# Cells.net
KiCad netlist of a schematic drawn in Altium Designer
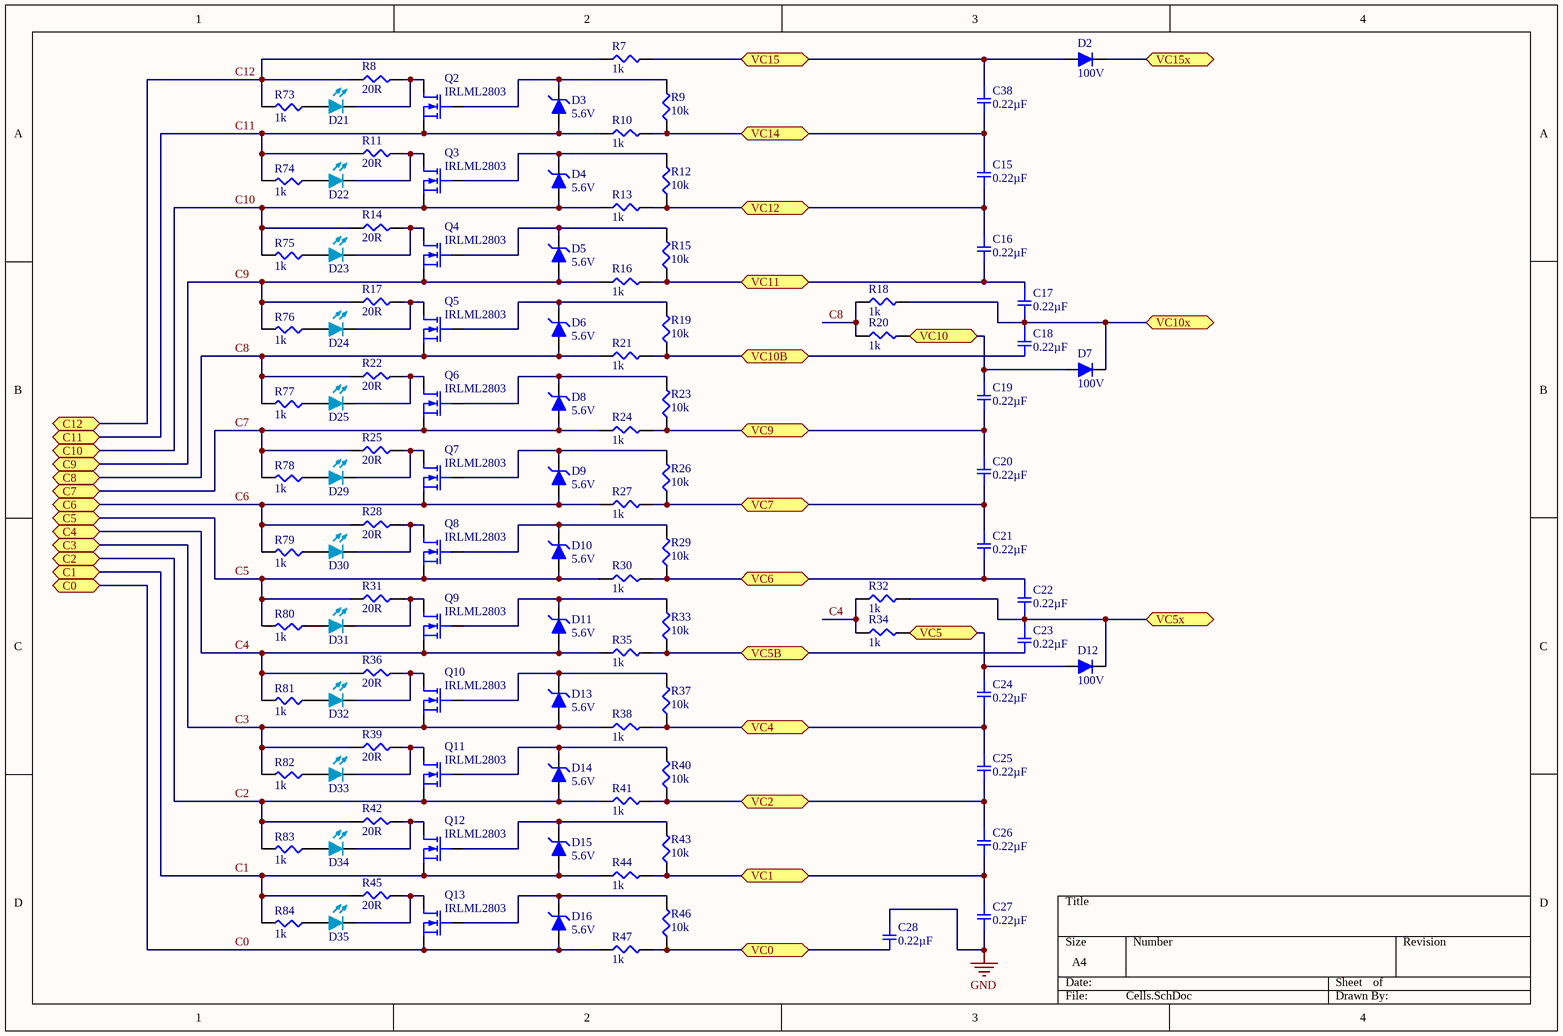
[diagram p0: Cells.SchDoc]

(export (version "E")
  (design (tool "Eeschema 10.0.6"))
  (components
    (comp (ref "C15")
      (value "0.22µF")
      (footprint "SMD-0603C")
      (description "CAP CER 0.22UF 25V X7R 0603")
      (fields
        (field (name "DIGI-KEY PART NUMBER") "490-5797-1-ND")
        (field (name "PART NUMBER") "GCJ188R71E224KA12D")
      )
      (libsource (lib "capacitor_murata_0603") (part "GCJ188R71E224KA12D"))
    )
    (comp (ref "C16")
      (value "0.22µF")
      (footprint "SMD-0603C")
      (description "CAP CER 0.22UF 25V X7R 0603")
      (fields
        (field (name "DIGI-KEY PART NUMBER") "490-5797-1-ND")
        (field (name "PART NUMBER") "GCJ188R71E224KA12D")
      )
      (libsource (lib "capacitor_murata_0603") (part "GCJ188R71E224KA12D"))
    )
    (comp (ref "C17")
      (value "0.22µF")
      (footprint "SMD-0603C")
      (description "CAP CER 0.22UF 25V X7R 0603")
      (fields
        (field (name "DIGI-KEY PART NUMBER") "490-5797-1-ND")
        (field (name "PART NUMBER") "GCJ188R71E224KA12D")
      )
      (libsource (lib "capacitor_murata_0603") (part "GCJ188R71E224KA12D"))
    )
    (comp (ref "C18")
      (value "0.22µF")
      (footprint "SMD-0603C")
      (description "CAP CER 0.22UF 25V X7R 0603")
      (fields
        (field (name "DIGI-KEY PART NUMBER") "490-5797-1-ND")
        (field (name "PART NUMBER") "GCJ188R71E224KA12D")
      )
      (libsource (lib "capacitor_murata_0603") (part "GCJ188R71E224KA12D"))
    )
    (comp (ref "C19")
      (value "0.22µF")
      (footprint "SMD-0603C")
      (description "CAP CER 0.22UF 25V X7R 0603")
      (fields
        (field (name "DIGI-KEY PART NUMBER") "490-5797-1-ND")
        (field (name "PART NUMBER") "GCJ188R71E224KA12D")
      )
      (libsource (lib "capacitor_murata_0603") (part "GCJ188R71E224KA12D"))
    )
    (comp (ref "C20")
      (value "0.22µF")
      (footprint "SMD-0603C")
      (description "CAP CER 0.22UF 25V X7R 0603")
      (fields
        (field (name "DIGI-KEY PART NUMBER") "490-5797-1-ND")
        (field (name "PART NUMBER") "GCJ188R71E224KA12D")
      )
      (libsource (lib "capacitor_murata_0603") (part "GCJ188R71E224KA12D"))
    )
    (comp (ref "C21")
      (value "0.22µF")
      (footprint "SMD-0603C")
      (description "CAP CER 0.22UF 25V X7R 0603")
      (fields
        (field (name "DIGI-KEY PART NUMBER") "490-5797-1-ND")
        (field (name "PART NUMBER") "GCJ188R71E224KA12D")
      )
      (libsource (lib "capacitor_murata_0603") (part "GCJ188R71E224KA12D"))
    )
    (comp (ref "C22")
      (value "0.22µF")
      (footprint "SMD-0603C")
      (description "CAP CER 0.22UF 25V X7R 0603")
      (fields
        (field (name "DIGI-KEY PART NUMBER") "490-5797-1-ND")
        (field (name "PART NUMBER") "GCJ188R71E224KA12D")
      )
      (libsource (lib "capacitor_murata_0603") (part "GCJ188R71E224KA12D"))
    )
    (comp (ref "C23")
      (value "0.22µF")
      (footprint "SMD-0603C")
      (description "CAP CER 0.22UF 25V X7R 0603")
      (fields
        (field (name "DIGI-KEY PART NUMBER") "490-5797-1-ND")
        (field (name "PART NUMBER") "GCJ188R71E224KA12D")
      )
      (libsource (lib "capacitor_murata_0603") (part "GCJ188R71E224KA12D"))
    )
    (comp (ref "C24")
      (value "0.22µF")
      (footprint "SMD-0603C")
      (description "CAP CER 0.22UF 25V X7R 0603")
      (fields
        (field (name "DIGI-KEY PART NUMBER") "490-5797-1-ND")
        (field (name "PART NUMBER") "GCJ188R71E224KA12D")
      )
      (libsource (lib "capacitor_murata_0603") (part "GCJ188R71E224KA12D"))
    )
    (comp (ref "C25")
      (value "0.22µF")
      (footprint "SMD-0603C")
      (description "CAP CER 0.22UF 25V X7R 0603")
      (fields
        (field (name "DIGI-KEY PART NUMBER") "490-5797-1-ND")
        (field (name "PART NUMBER") "GCJ188R71E224KA12D")
      )
      (libsource (lib "capacitor_murata_0603") (part "GCJ188R71E224KA12D"))
    )
    (comp (ref "C26")
      (value "0.22µF")
      (footprint "SMD-0603C")
      (description "CAP CER 0.22UF 25V X7R 0603")
      (fields
        (field (name "DIGI-KEY PART NUMBER") "490-5797-1-ND")
        (field (name "PART NUMBER") "GCJ188R71E224KA12D")
      )
      (libsource (lib "capacitor_murata_0603") (part "GCJ188R71E224KA12D"))
    )
    (comp (ref "C27")
      (value "0.22µF")
      (footprint "SMD-0603C")
      (description "CAP CER 0.22UF 25V X7R 0603")
      (fields
        (field (name "DIGI-KEY PART NUMBER") "490-5797-1-ND")
        (field (name "PART NUMBER") "GCJ188R71E224KA12D")
      )
      (libsource (lib "capacitor_murata_0603") (part "GCJ188R71E224KA12D"))
    )
    (comp (ref "C28")
      (value "0.22µF")
      (footprint "SMD-0603C")
      (description "CAP CER 0.22UF 25V X7R 0603")
      (fields
        (field (name "DIGI-KEY PART NUMBER") "490-5797-1-ND")
        (field (name "PART NUMBER") "GCJ188R71E224KA12D")
      )
      (libsource (lib "capacitor_murata_0603") (part "GCJ188R71E224KA12D"))
    )
    (comp (ref "C38")
      (value "0.22µF")
      (footprint "SMD-0603C")
      (description "CAP CER 0.22UF 25V X7R 0603")
      (fields
        (field (name "DIGI-KEY PART NUMBER") "490-5797-1-ND")
        (field (name "PART NUMBER") "GCJ188R71E224KA12D")
      )
      (libsource (lib "capacitor_murata_0603") (part "GCJ188R71E224KA12D"))
    )
    (comp (ref "D2")
      (value "100V")
      (footprint "SOD-323")
      (description "Diode")
      (libsource (lib "Components") (part "DIODE"))
    )
    (comp (ref "D3")
      (value "5.6V")
      (footprint "SOD-323")
      (description "Zener Diode 5.6V")
      (libsource (lib "Components") (part "ZENER_5V6"))
    )
    (comp (ref "D4")
      (value "5.6V")
      (footprint "SOD-323")
      (description "Zener Diode 5.6V")
      (libsource (lib "Components") (part "ZENER_5V6"))
    )
    (comp (ref "D5")
      (value "5.6V")
      (footprint "SOD-323")
      (description "Zener Diode 5.6V")
      (libsource (lib "Components") (part "ZENER_5V6"))
    )
    (comp (ref "D6")
      (value "5.6V")
      (footprint "SOD-323")
      (description "Zener Diode 5.6V")
      (libsource (lib "Components") (part "ZENER_5V6"))
    )
    (comp (ref "D7")
      (value "100V")
      (footprint "SOD-323")
      (description "Diode")
      (libsource (lib "Components") (part "DIODE"))
    )
    (comp (ref "D8")
      (value "5.6V")
      (footprint "SOD-323")
      (description "Zener Diode 5.6V")
      (libsource (lib "Components") (part "ZENER_5V6"))
    )
    (comp (ref "D9")
      (value "5.6V")
      (footprint "SOD-323")
      (description "Zener Diode 5.6V")
      (libsource (lib "Components") (part "ZENER_5V6"))
    )
    (comp (ref "D10")
      (value "5.6V")
      (footprint "SOD-323")
      (description "Zener Diode 5.6V")
      (libsource (lib "Components") (part "ZENER_5V6"))
    )
    (comp (ref "D11")
      (value "5.6V")
      (footprint "SOD-323")
      (description "Zener Diode 5.6V")
      (libsource (lib "Components") (part "ZENER_5V6"))
    )
    (comp (ref "D12")
      (value "100V")
      (footprint "SOD-323")
      (description "Diode")
      (libsource (lib "Components") (part "DIODE"))
    )
    (comp (ref "D13")
      (value "5.6V")
      (footprint "SOD-323")
      (description "Zener Diode 5.6V")
      (libsource (lib "Components") (part "ZENER_5V6"))
    )
    (comp (ref "D14")
      (value "5.6V")
      (footprint "SOD-323")
      (description "Zener Diode 5.6V")
      (libsource (lib "Components") (part "ZENER_5V6"))
    )
    (comp (ref "D15")
      (value "5.6V")
      (footprint "SOD-323")
      (description "Zener Diode 5.6V")
      (libsource (lib "Components") (part "ZENER_5V6"))
    )
    (comp (ref "D16")
      (value "5.6V")
      (footprint "SOD-323")
      (description "Zener Diode 5.6V")
      (libsource (lib "Components") (part "ZENER_5V6"))
    )
    (comp (ref "D21")
      (value "LED")
      (footprint "LED0603")
      (fields (field (name "PARTNUMBER") "LTST-C193TGKT-5A") (field (name "MANUFACTURER") "Lite-On Inc."))
      (libsource (lib "Components") (part "LED_BLUE"))
    )
    (comp (ref "D22")
      (value "LED")
      (footprint "LED0603")
      (fields (field (name "PARTNUMBER") "LTST-C193TGKT-5A") (field (name "MANUFACTURER") "Lite-On Inc."))
      (libsource (lib "Components") (part "LED_BLUE"))
    )
    (comp (ref "D23")
      (value "LED")
      (footprint "LED0603")
      (fields (field (name "PARTNUMBER") "LTST-C193TGKT-5A") (field (name "MANUFACTURER") "Lite-On Inc."))
      (libsource (lib "Components") (part "LED_BLUE"))
    )
    (comp (ref "D24")
      (value "LED")
      (footprint "LED0603")
      (fields (field (name "PARTNUMBER") "LTST-C193TGKT-5A") (field (name "MANUFACTURER") "Lite-On Inc."))
      (libsource (lib "Components") (part "LED_BLUE"))
    )
    (comp (ref "D25")
      (value "LED")
      (footprint "LED0603")
      (fields (field (name "PARTNUMBER") "LTST-C193TGKT-5A") (field (name "MANUFACTURER") "Lite-On Inc."))
      (libsource (lib "Components") (part "LED_BLUE"))
    )
    (comp (ref "D29")
      (value "LED")
      (footprint "LED0603")
      (fields (field (name "PARTNUMBER") "LTST-C193TGKT-5A") (field (name "MANUFACTURER") "Lite-On Inc."))
      (libsource (lib "Components") (part "LED_BLUE"))
    )
    (comp (ref "D30")
      (value "LED")
      (footprint "LED0603")
      (fields (field (name "PARTNUMBER") "LTST-C193TGKT-5A") (field (name "MANUFACTURER") "Lite-On Inc."))
      (libsource (lib "Components") (part "LED_BLUE"))
    )
    (comp (ref "D31")
      (value "LED")
      (footprint "LED0603")
      (fields (field (name "PARTNUMBER") "LTST-C193TGKT-5A") (field (name "MANUFACTURER") "Lite-On Inc."))
      (libsource (lib "Components") (part "LED_BLUE"))
    )
    (comp (ref "D32")
      (value "LED")
      (footprint "LED0603")
      (fields (field (name "PARTNUMBER") "LTST-C193TGKT-5A") (field (name "MANUFACTURER") "Lite-On Inc."))
      (libsource (lib "Components") (part "LED_BLUE"))
    )
    (comp (ref "D33")
      (value "LED")
      (footprint "LED0603")
      (fields (field (name "PARTNUMBER") "LTST-C193TGKT-5A") (field (name "MANUFACTURER") "Lite-On Inc."))
      (libsource (lib "Components") (part "LED_BLUE"))
    )
    (comp (ref "D34")
      (value "LED")
      (footprint "LED0603")
      (fields (field (name "PARTNUMBER") "LTST-C193TGKT-5A") (field (name "MANUFACTURER") "Lite-On Inc."))
      (libsource (lib "Components") (part "LED_BLUE"))
    )
    (comp (ref "D35")
      (value "LED")
      (footprint "LED0603")
      (fields (field (name "PARTNUMBER") "LTST-C193TGKT-5A") (field (name "MANUFACTURER") "Lite-On Inc."))
      (libsource (lib "Components") (part "LED_BLUE"))
    )
    (comp (ref "Q2")
      (value "IRLML2803")
      (footprint "SOT23-3")
      (description "N-Channel MOSFET")
      (fields (field (name "PUBLISHER") "Altium Limited"))
      (libsource (lib "Components") (part "MOSFET-N"))
    )
    (comp (ref "Q3")
      (value "IRLML2803")
      (footprint "SOT23-3")
      (description "N-Channel MOSFET")
      (fields (field (name "PUBLISHER") "Altium Limited"))
      (libsource (lib "Components") (part "MOSFET-N"))
    )
    (comp (ref "Q4")
      (value "IRLML2803")
      (footprint "SOT23-3")
      (description "N-Channel MOSFET")
      (fields (field (name "PUBLISHER") "Altium Limited"))
      (libsource (lib "Components") (part "MOSFET-N"))
    )
    (comp (ref "Q5")
      (value "IRLML2803")
      (footprint "SOT23-3")
      (description "N-Channel MOSFET")
      (fields (field (name "PUBLISHER") "Altium Limited"))
      (libsource (lib "Components") (part "MOSFET-N"))
    )
    (comp (ref "Q6")
      (value "IRLML2803")
      (footprint "SOT23-3")
      (description "N-Channel MOSFET")
      (fields (field (name "PUBLISHER") "Altium Limited"))
      (libsource (lib "Components") (part "MOSFET-N"))
    )
    (comp (ref "Q7")
      (value "IRLML2803")
      (footprint "SOT23-3")
      (description "N-Channel MOSFET")
      (fields (field (name "PUBLISHER") "Altium Limited"))
      (libsource (lib "Components") (part "MOSFET-N"))
    )
    (comp (ref "Q8")
      (value "IRLML2803")
      (footprint "SOT23-3")
      (description "N-Channel MOSFET")
      (fields (field (name "PUBLISHER") "Altium Limited"))
      (libsource (lib "Components") (part "MOSFET-N"))
    )
    (comp (ref "Q9")
      (value "IRLML2803")
      (footprint "SOT23-3")
      (description "N-Channel MOSFET")
      (fields (field (name "PUBLISHER") "Altium Limited"))
      (libsource (lib "Components") (part "MOSFET-N"))
    )
    (comp (ref "Q10")
      (value "IRLML2803")
      (footprint "SOT23-3")
      (description "N-Channel MOSFET")
      (fields (field (name "PUBLISHER") "Altium Limited"))
      (libsource (lib "Components") (part "MOSFET-N"))
    )
    (comp (ref "Q11")
      (value "IRLML2803")
      (footprint "SOT23-3")
      (description "N-Channel MOSFET")
      (fields (field (name "PUBLISHER") "Altium Limited"))
      (libsource (lib "Components") (part "MOSFET-N"))
    )
    (comp (ref "Q12")
      (value "IRLML2803")
      (footprint "SOT23-3")
      (description "N-Channel MOSFET")
      (fields (field (name "PUBLISHER") "Altium Limited"))
      (libsource (lib "Components") (part "MOSFET-N"))
    )
    (comp (ref "Q13")
      (value "IRLML2803")
      (footprint "SOT23-3")
      (description "N-Channel MOSFET")
      (fields (field (name "PUBLISHER") "Altium Limited"))
      (libsource (lib "Components") (part "MOSFET-N"))
    )
    (comp (ref "R7")
      (value "1k")
      (footprint "SMD-0603-RES")
      (description "RES SMD 1K OHM 1% 1/10W 0603")
      (fields
        (field (name "PART NUMBER") "ERJ-3EKF1001V")
        (field (name "DIGI-KEY PART NUMBER") "P1.00KHCT-ND")
      )
      (libsource (lib "Panasonic_ERJ_0603") (part "ERJ-3EKF1001V"))
    )
    (comp (ref "R8")
      (value "20R")
      (footprint "SMD-1206-RES")
      (description "RES SMD 20 OHM 1% 1/4W 1206")
      (fields
        (field (name "PART NUMBER") "ERJ-8ENF20R0V")
        (field (name "DIGI-KEY PART NUMBER") "P20.0FCT-ND")
      )
      (libsource (lib "Panasonic_ERJ_1206") (part "ERJ-8ENF20R0V"))
    )
    (comp (ref "R9")
      (value "10k")
      (footprint "SMD-0603-RES")
      (description "RES SMD 10K OHM 1% 1/10W 0603")
      (fields
        (field (name "PART NUMBER") "ERJ-3EKF1002V")
        (field (name "DIGI-KEY PART NUMBER") "P10.0KHCT-ND")
      )
      (libsource (lib "Panasonic_ERJ_0603") (part "ERJ-3EKF1002V"))
    )
    (comp (ref "R10")
      (value "1k")
      (footprint "SMD-0603-RES")
      (description "RES SMD 1K OHM 1% 1/10W 0603")
      (fields
        (field (name "PART NUMBER") "ERJ-3EKF1001V")
        (field (name "DIGI-KEY PART NUMBER") "P1.00KHCT-ND")
      )
      (libsource (lib "Panasonic_ERJ_0603") (part "ERJ-3EKF1001V"))
    )
    (comp (ref "R11")
      (value "20R")
      (footprint "SMD-1206-RES")
      (description "RES SMD 20 OHM 1% 1/4W 1206")
      (fields
        (field (name "PART NUMBER") "ERJ-8ENF20R0V")
        (field (name "DIGI-KEY PART NUMBER") "P20.0FCT-ND")
      )
      (libsource (lib "Panasonic_ERJ_1206") (part "ERJ-8ENF20R0V"))
    )
    (comp (ref "R12")
      (value "10k")
      (footprint "SMD-0603-RES")
      (description "RES SMD 10K OHM 1% 1/10W 0603")
      (fields
        (field (name "PART NUMBER") "ERJ-3EKF1002V")
        (field (name "DIGI-KEY PART NUMBER") "P10.0KHCT-ND")
      )
      (libsource (lib "Panasonic_ERJ_0603") (part "ERJ-3EKF1002V"))
    )
    (comp (ref "R13")
      (value "1k")
      (footprint "SMD-0603-RES")
      (description "RES SMD 1K OHM 1% 1/10W 0603")
      (fields
        (field (name "PART NUMBER") "ERJ-3EKF1001V")
        (field (name "DIGI-KEY PART NUMBER") "P1.00KHCT-ND")
      )
      (libsource (lib "Panasonic_ERJ_0603") (part "ERJ-3EKF1001V"))
    )
    (comp (ref "R14")
      (value "20R")
      (footprint "SMD-1206-RES")
      (description "RES SMD 20 OHM 1% 1/4W 1206")
      (fields
        (field (name "PART NUMBER") "ERJ-8ENF20R0V")
        (field (name "DIGI-KEY PART NUMBER") "P20.0FCT-ND")
      )
      (libsource (lib "Panasonic_ERJ_1206") (part "ERJ-8ENF20R0V"))
    )
    (comp (ref "R15")
      (value "10k")
      (footprint "SMD-0603-RES")
      (description "RES SMD 10K OHM 1% 1/10W 0603")
      (fields
        (field (name "PART NUMBER") "ERJ-3EKF1002V")
        (field (name "DIGI-KEY PART NUMBER") "P10.0KHCT-ND")
      )
      (libsource (lib "Panasonic_ERJ_0603") (part "ERJ-3EKF1002V"))
    )
    (comp (ref "R16")
      (value "1k")
      (footprint "SMD-0603-RES")
      (description "RES SMD 1K OHM 1% 1/10W 0603")
      (fields
        (field (name "PART NUMBER") "ERJ-3EKF1001V")
        (field (name "DIGI-KEY PART NUMBER") "P1.00KHCT-ND")
      )
      (libsource (lib "Panasonic_ERJ_0603") (part "ERJ-3EKF1001V"))
    )
    (comp (ref "R17")
      (value "20R")
      (footprint "SMD-1206-RES")
      (description "RES SMD 20 OHM 1% 1/4W 1206")
      (fields
        (field (name "PART NUMBER") "ERJ-8ENF20R0V")
        (field (name "DIGI-KEY PART NUMBER") "P20.0FCT-ND")
      )
      (libsource (lib "Panasonic_ERJ_1206") (part "ERJ-8ENF20R0V"))
    )
    (comp (ref "R18")
      (value "1k")
      (footprint "SMD-0603-RES")
      (description "RES SMD 1K OHM 1% 1/10W 0603")
      (fields
        (field (name "PART NUMBER") "ERJ-3EKF1001V")
        (field (name "DIGI-KEY PART NUMBER") "P1.00KHCT-ND")
      )
      (libsource (lib "Panasonic_ERJ_0603") (part "ERJ-3EKF1001V"))
    )
    (comp (ref "R19")
      (value "10k")
      (footprint "SMD-0603-RES")
      (description "RES SMD 10K OHM 1% 1/10W 0603")
      (fields
        (field (name "PART NUMBER") "ERJ-3EKF1002V")
        (field (name "DIGI-KEY PART NUMBER") "P10.0KHCT-ND")
      )
      (libsource (lib "Panasonic_ERJ_0603") (part "ERJ-3EKF1002V"))
    )
    (comp (ref "R20")
      (value "1k")
      (footprint "SMD-0603-RES")
      (description "RES SMD 1K OHM 1% 1/10W 0603")
      (fields
        (field (name "PART NUMBER") "ERJ-3EKF1001V")
        (field (name "DIGI-KEY PART NUMBER") "P1.00KHCT-ND")
      )
      (libsource (lib "Panasonic_ERJ_0603") (part "ERJ-3EKF1001V"))
    )
    (comp (ref "R21")
      (value "1k")
      (footprint "SMD-0603-RES")
      (description "RES SMD 1K OHM 1% 1/10W 0603")
      (fields
        (field (name "PART NUMBER") "ERJ-3EKF1001V")
        (field (name "DIGI-KEY PART NUMBER") "P1.00KHCT-ND")
      )
      (libsource (lib "Panasonic_ERJ_0603") (part "ERJ-3EKF1001V"))
    )
    (comp (ref "R22")
      (value "20R")
      (footprint "SMD-1206-RES")
      (description "RES SMD 20 OHM 1% 1/4W 1206")
      (fields
        (field (name "PART NUMBER") "ERJ-8ENF20R0V")
        (field (name "DIGI-KEY PART NUMBER") "P20.0FCT-ND")
      )
      (libsource (lib "Panasonic_ERJ_1206") (part "ERJ-8ENF20R0V"))
    )
    (comp (ref "R23")
      (value "10k")
      (footprint "SMD-0603-RES")
      (description "RES SMD 10K OHM 1% 1/10W 0603")
      (fields
        (field (name "PART NUMBER") "ERJ-3EKF1002V")
        (field (name "DIGI-KEY PART NUMBER") "P10.0KHCT-ND")
      )
      (libsource (lib "Panasonic_ERJ_0603") (part "ERJ-3EKF1002V"))
    )
    (comp (ref "R24")
      (value "1k")
      (footprint "SMD-0603-RES")
      (description "RES SMD 1K OHM 1% 1/10W 0603")
      (fields
        (field (name "PART NUMBER") "ERJ-3EKF1001V")
        (field (name "DIGI-KEY PART NUMBER") "P1.00KHCT-ND")
      )
      (libsource (lib "Panasonic_ERJ_0603") (part "ERJ-3EKF1001V"))
    )
    (comp (ref "R25")
      (value "20R")
      (footprint "SMD-1206-RES")
      (description "RES SMD 20 OHM 1% 1/4W 1206")
      (fields
        (field (name "PART NUMBER") "ERJ-8ENF20R0V")
        (field (name "DIGI-KEY PART NUMBER") "P20.0FCT-ND")
      )
      (libsource (lib "Panasonic_ERJ_1206") (part "ERJ-8ENF20R0V"))
    )
    (comp (ref "R26")
      (value "10k")
      (footprint "SMD-0603-RES")
      (description "RES SMD 10K OHM 1% 1/10W 0603")
      (fields
        (field (name "PART NUMBER") "ERJ-3EKF1002V")
        (field (name "DIGI-KEY PART NUMBER") "P10.0KHCT-ND")
      )
      (libsource (lib "Panasonic_ERJ_0603") (part "ERJ-3EKF1002V"))
    )
    (comp (ref "R27")
      (value "1k")
      (footprint "SMD-0603-RES")
      (description "RES SMD 1K OHM 1% 1/10W 0603")
      (fields
        (field (name "PART NUMBER") "ERJ-3EKF1001V")
        (field (name "DIGI-KEY PART NUMBER") "P1.00KHCT-ND")
      )
      (libsource (lib "Panasonic_ERJ_0603") (part "ERJ-3EKF1001V"))
    )
    (comp (ref "R28")
      (value "20R")
      (footprint "SMD-1206-RES")
      (description "RES SMD 20 OHM 1% 1/4W 1206")
      (fields
        (field (name "PART NUMBER") "ERJ-8ENF20R0V")
        (field (name "DIGI-KEY PART NUMBER") "P20.0FCT-ND")
      )
      (libsource (lib "Panasonic_ERJ_1206") (part "ERJ-8ENF20R0V"))
    )
    (comp (ref "R29")
      (value "10k")
      (footprint "SMD-0603-RES")
      (description "RES SMD 10K OHM 1% 1/10W 0603")
      (fields
        (field (name "PART NUMBER") "ERJ-3EKF1002V")
        (field (name "DIGI-KEY PART NUMBER") "P10.0KHCT-ND")
      )
      (libsource (lib "Panasonic_ERJ_0603") (part "ERJ-3EKF1002V"))
    )
    (comp (ref "R30")
      (value "1k")
      (footprint "SMD-0603-RES")
      (description "RES SMD 1K OHM 1% 1/10W 0603")
      (fields
        (field (name "PART NUMBER") "ERJ-3EKF1001V")
        (field (name "DIGI-KEY PART NUMBER") "P1.00KHCT-ND")
      )
      (libsource (lib "Panasonic_ERJ_0603") (part "ERJ-3EKF1001V"))
    )
    (comp (ref "R31")
      (value "20R")
      (footprint "SMD-1206-RES")
      (description "RES SMD 20 OHM 1% 1/4W 1206")
      (fields
        (field (name "PART NUMBER") "ERJ-8ENF20R0V")
        (field (name "DIGI-KEY PART NUMBER") "P20.0FCT-ND")
      )
      (libsource (lib "Panasonic_ERJ_1206") (part "ERJ-8ENF20R0V"))
    )
    (comp (ref "R32")
      (value "1k")
      (footprint "SMD-0603-RES")
      (description "RES SMD 1K OHM 1% 1/10W 0603")
      (fields
        (field (name "PART NUMBER") "ERJ-3EKF1001V")
        (field (name "DIGI-KEY PART NUMBER") "P1.00KHCT-ND")
      )
      (libsource (lib "Panasonic_ERJ_0603") (part "ERJ-3EKF1001V"))
    )
    (comp (ref "R33")
      (value "10k")
      (footprint "SMD-0603-RES")
      (description "RES SMD 10K OHM 1% 1/10W 0603")
      (fields
        (field (name "PART NUMBER") "ERJ-3EKF1002V")
        (field (name "DIGI-KEY PART NUMBER") "P10.0KHCT-ND")
      )
      (libsource (lib "Panasonic_ERJ_0603") (part "ERJ-3EKF1002V"))
    )
    (comp (ref "R34")
      (value "1k")
      (footprint "SMD-0603-RES")
      (description "RES SMD 1K OHM 1% 1/10W 0603")
      (fields
        (field (name "PART NUMBER") "ERJ-3EKF1001V")
        (field (name "DIGI-KEY PART NUMBER") "P1.00KHCT-ND")
      )
      (libsource (lib "Panasonic_ERJ_0603") (part "ERJ-3EKF1001V"))
    )
    (comp (ref "R35")
      (value "1k")
      (footprint "SMD-0603-RES")
      (description "RES SMD 1K OHM 1% 1/10W 0603")
      (fields
        (field (name "PART NUMBER") "ERJ-3EKF1001V")
        (field (name "DIGI-KEY PART NUMBER") "P1.00KHCT-ND")
      )
      (libsource (lib "Panasonic_ERJ_0603") (part "ERJ-3EKF1001V"))
    )
    (comp (ref "R36")
      (value "20R")
      (footprint "SMD-1206-RES")
      (description "RES SMD 20 OHM 1% 1/4W 1206")
      (fields
        (field (name "PART NUMBER") "ERJ-8ENF20R0V")
        (field (name "DIGI-KEY PART NUMBER") "P20.0FCT-ND")
      )
      (libsource (lib "Panasonic_ERJ_1206") (part "ERJ-8ENF20R0V"))
    )
    (comp (ref "R37")
      (value "10k")
      (footprint "SMD-0603-RES")
      (description "RES SMD 10K OHM 1% 1/10W 0603")
      (fields
        (field (name "PART NUMBER") "ERJ-3EKF1002V")
        (field (name "DIGI-KEY PART NUMBER") "P10.0KHCT-ND")
      )
      (libsource (lib "Panasonic_ERJ_0603") (part "ERJ-3EKF1002V"))
    )
    (comp (ref "R38")
      (value "1k")
      (footprint "SMD-0603-RES")
      (description "RES SMD 1K OHM 1% 1/10W 0603")
      (fields
        (field (name "PART NUMBER") "ERJ-3EKF1001V")
        (field (name "DIGI-KEY PART NUMBER") "P1.00KHCT-ND")
      )
      (libsource (lib "Panasonic_ERJ_0603") (part "ERJ-3EKF1001V"))
    )
    (comp (ref "R39")
      (value "20R")
      (footprint "SMD-1206-RES")
      (description "RES SMD 20 OHM 1% 1/4W 1206")
      (fields
        (field (name "PART NUMBER") "ERJ-8ENF20R0V")
        (field (name "DIGI-KEY PART NUMBER") "P20.0FCT-ND")
      )
      (libsource (lib "Panasonic_ERJ_1206") (part "ERJ-8ENF20R0V"))
    )
    (comp (ref "R40")
      (value "10k")
      (footprint "SMD-0603-RES")
      (description "RES SMD 10K OHM 1% 1/10W 0603")
      (fields
        (field (name "PART NUMBER") "ERJ-3EKF1002V")
        (field (name "DIGI-KEY PART NUMBER") "P10.0KHCT-ND")
      )
      (libsource (lib "Panasonic_ERJ_0603") (part "ERJ-3EKF1002V"))
    )
    (comp (ref "R41")
      (value "1k")
      (footprint "SMD-0603-RES")
      (description "RES SMD 1K OHM 1% 1/10W 0603")
      (fields
        (field (name "PART NUMBER") "ERJ-3EKF1001V")
        (field (name "DIGI-KEY PART NUMBER") "P1.00KHCT-ND")
      )
      (libsource (lib "Panasonic_ERJ_0603") (part "ERJ-3EKF1001V"))
    )
    (comp (ref "R42")
      (value "20R")
      (footprint "SMD-1206-RES")
      (description "RES SMD 20 OHM 1% 1/4W 1206")
      (fields
        (field (name "PART NUMBER") "ERJ-8ENF20R0V")
        (field (name "DIGI-KEY PART NUMBER") "P20.0FCT-ND")
      )
      (libsource (lib "Panasonic_ERJ_1206") (part "ERJ-8ENF20R0V"))
    )
    (comp (ref "R43")
      (value "10k")
      (footprint "SMD-0603-RES")
      (description "RES SMD 10K OHM 1% 1/10W 0603")
      (fields
        (field (name "PART NUMBER") "ERJ-3EKF1002V")
        (field (name "DIGI-KEY PART NUMBER") "P10.0KHCT-ND")
      )
      (libsource (lib "Panasonic_ERJ_0603") (part "ERJ-3EKF1002V"))
    )
    (comp (ref "R44")
      (value "1k")
      (footprint "SMD-0603-RES")
      (description "RES SMD 1K OHM 1% 1/10W 0603")
      (fields
        (field (name "PART NUMBER") "ERJ-3EKF1001V")
        (field (name "DIGI-KEY PART NUMBER") "P1.00KHCT-ND")
      )
      (libsource (lib "Panasonic_ERJ_0603") (part "ERJ-3EKF1001V"))
    )
    (comp (ref "R45")
      (value "20R")
      (footprint "SMD-1206-RES")
      (description "RES SMD 20 OHM 1% 1/4W 1206")
      (fields
        (field (name "PART NUMBER") "ERJ-8ENF20R0V")
        (field (name "DIGI-KEY PART NUMBER") "P20.0FCT-ND")
      )
      (libsource (lib "Panasonic_ERJ_1206") (part "ERJ-8ENF20R0V"))
    )
    (comp (ref "R46")
      (value "10k")
      (footprint "SMD-0603-RES")
      (description "RES SMD 10K OHM 1% 1/10W 0603")
      (fields
        (field (name "PART NUMBER") "ERJ-3EKF1002V")
        (field (name "DIGI-KEY PART NUMBER") "P10.0KHCT-ND")
      )
      (libsource (lib "Panasonic_ERJ_0603") (part "ERJ-3EKF1002V"))
    )
    (comp (ref "R47")
      (value "1k")
      (footprint "SMD-0603-RES")
      (description "RES SMD 1K OHM 1% 1/10W 0603")
      (fields
        (field (name "PART NUMBER") "ERJ-3EKF1001V")
        (field (name "DIGI-KEY PART NUMBER") "P1.00KHCT-ND")
      )
      (libsource (lib "Panasonic_ERJ_0603") (part "ERJ-3EKF1001V"))
    )
    (comp (ref "R73")
      (value "1k")
      (footprint "SMD-0603-RES")
      (description "RES SMD 1K OHM 1% 1/10W 0603")
      (fields
        (field (name "PART NUMBER") "ERJ-3EKF1001V")
        (field (name "DIGI-KEY PART NUMBER") "P1.00KHCT-ND")
      )
      (libsource (lib "Panasonic_ERJ_0603") (part "ERJ-3EKF1001V"))
    )
    (comp (ref "R74")
      (value "1k")
      (footprint "SMD-0603-RES")
      (description "RES SMD 1K OHM 1% 1/10W 0603")
      (fields
        (field (name "PART NUMBER") "ERJ-3EKF1001V")
        (field (name "DIGI-KEY PART NUMBER") "P1.00KHCT-ND")
      )
      (libsource (lib "Panasonic_ERJ_0603") (part "ERJ-3EKF1001V"))
    )
    (comp (ref "R75")
      (value "1k")
      (footprint "SMD-0603-RES")
      (description "RES SMD 1K OHM 1% 1/10W 0603")
      (fields
        (field (name "PART NUMBER") "ERJ-3EKF1001V")
        (field (name "DIGI-KEY PART NUMBER") "P1.00KHCT-ND")
      )
      (libsource (lib "Panasonic_ERJ_0603") (part "ERJ-3EKF1001V"))
    )
    (comp (ref "R76")
      (value "1k")
      (footprint "SMD-0603-RES")
      (description "RES SMD 1K OHM 1% 1/10W 0603")
      (fields
        (field (name "PART NUMBER") "ERJ-3EKF1001V")
        (field (name "DIGI-KEY PART NUMBER") "P1.00KHCT-ND")
      )
      (libsource (lib "Panasonic_ERJ_0603") (part "ERJ-3EKF1001V"))
    )
    (comp (ref "R77")
      (value "1k")
      (footprint "SMD-0603-RES")
      (description "RES SMD 1K OHM 1% 1/10W 0603")
      (fields
        (field (name "PART NUMBER") "ERJ-3EKF1001V")
        (field (name "DIGI-KEY PART NUMBER") "P1.00KHCT-ND")
      )
      (libsource (lib "Panasonic_ERJ_0603") (part "ERJ-3EKF1001V"))
    )
    (comp (ref "R78")
      (value "1k")
      (footprint "SMD-0603-RES")
      (description "RES SMD 1K OHM 1% 1/10W 0603")
      (fields
        (field (name "PART NUMBER") "ERJ-3EKF1001V")
        (field (name "DIGI-KEY PART NUMBER") "P1.00KHCT-ND")
      )
      (libsource (lib "Panasonic_ERJ_0603") (part "ERJ-3EKF1001V"))
    )
    (comp (ref "R79")
      (value "1k")
      (footprint "SMD-0603-RES")
      (description "RES SMD 1K OHM 1% 1/10W 0603")
      (fields
        (field (name "PART NUMBER") "ERJ-3EKF1001V")
        (field (name "DIGI-KEY PART NUMBER") "P1.00KHCT-ND")
      )
      (libsource (lib "Panasonic_ERJ_0603") (part "ERJ-3EKF1001V"))
    )
    (comp (ref "R80")
      (value "1k")
      (footprint "SMD-0603-RES")
      (description "RES SMD 1K OHM 1% 1/10W 0603")
      (fields
        (field (name "PART NUMBER") "ERJ-3EKF1001V")
        (field (name "DIGI-KEY PART NUMBER") "P1.00KHCT-ND")
      )
      (libsource (lib "Panasonic_ERJ_0603") (part "ERJ-3EKF1001V"))
    )
    (comp (ref "R81")
      (value "1k")
      (footprint "SMD-0603-RES")
      (description "RES SMD 1K OHM 1% 1/10W 0603")
      (fields
        (field (name "PART NUMBER") "ERJ-3EKF1001V")
        (field (name "DIGI-KEY PART NUMBER") "P1.00KHCT-ND")
      )
      (libsource (lib "Panasonic_ERJ_0603") (part "ERJ-3EKF1001V"))
    )
    (comp (ref "R82")
      (value "1k")
      (footprint "SMD-0603-RES")
      (description "RES SMD 1K OHM 1% 1/10W 0603")
      (fields
        (field (name "PART NUMBER") "ERJ-3EKF1001V")
        (field (name "DIGI-KEY PART NUMBER") "P1.00KHCT-ND")
      )
      (libsource (lib "Panasonic_ERJ_0603") (part "ERJ-3EKF1001V"))
    )
    (comp (ref "R83")
      (value "1k")
      (footprint "SMD-0603-RES")
      (description "RES SMD 1K OHM 1% 1/10W 0603")
      (fields
        (field (name "PART NUMBER") "ERJ-3EKF1001V")
        (field (name "DIGI-KEY PART NUMBER") "P1.00KHCT-ND")
      )
      (libsource (lib "Panasonic_ERJ_0603") (part "ERJ-3EKF1001V"))
    )
    (comp (ref "R84")
      (value "1k")
      (footprint "SMD-0603-RES")
      (description "RES SMD 1K OHM 1% 1/10W 0603")
      (fields
        (field (name "PART NUMBER") "ERJ-3EKF1001V")
        (field (name "DIGI-KEY PART NUMBER") "P1.00KHCT-ND")
      )
      (libsource (lib "Panasonic_ERJ_0603") (part "ERJ-3EKF1001V"))
    )
  )
  (nets
    (net (code "1") (name "/C0") (class "Default")
      (node (ref "D16") (pin "2") (pinfunction "A_2") (pintype "passive"))
      (node (ref "Q13") (pin "2") (pinfunction "S_2") (pintype "passive"))
      (node (ref "R47") (pin "1") (pinfunction "1_1") (pintype "passive"))
    )
    (net (code "2") (name "/C1") (class "Default")
      (node (ref "D15") (pin "2") (pinfunction "A_2") (pintype "passive"))
      (node (ref "Q12") (pin "2") (pinfunction "S_2") (pintype "passive"))
      (node (ref "R44") (pin "1") (pinfunction "1_1") (pintype "passive"))
      (node (ref "R45") (pin "1") (pinfunction "1_1") (pintype "passive"))
      (node (ref "R84") (pin "2") (pinfunction "2_2") (pintype "passive"))
    )
    (net (code "3") (name "/C2") (class "Default")
      (node (ref "D14") (pin "2") (pinfunction "A_2") (pintype "passive"))
      (node (ref "Q11") (pin "2") (pinfunction "S_2") (pintype "passive"))
      (node (ref "R41") (pin "1") (pinfunction "1_1") (pintype "passive"))
      (node (ref "R42") (pin "1") (pinfunction "1_1") (pintype "passive"))
      (node (ref "R83") (pin "2") (pinfunction "2_2") (pintype "passive"))
    )
    (net (code "4") (name "/C3") (class "Default")
      (node (ref "D13") (pin "2") (pinfunction "A_2") (pintype "passive"))
      (node (ref "Q10") (pin "2") (pinfunction "S_2") (pintype "passive"))
      (node (ref "R38") (pin "1") (pinfunction "1_1") (pintype "passive"))
      (node (ref "R39") (pin "1") (pinfunction "1_1") (pintype "passive"))
      (node (ref "R82") (pin "2") (pinfunction "2_2") (pintype "passive"))
    )
    (net (code "5") (name "/C4") (class "Default")
      (node (ref "D11") (pin "2") (pinfunction "A_2") (pintype "passive"))
      (node (ref "Q9") (pin "2") (pinfunction "S_2") (pintype "passive"))
      (node (ref "R32") (pin "1") (pinfunction "1_1") (pintype "passive"))
      (node (ref "R34") (pin "1") (pinfunction "1_1") (pintype "passive"))
      (node (ref "R35") (pin "1") (pinfunction "1_1") (pintype "passive"))
      (node (ref "R36") (pin "1") (pinfunction "1_1") (pintype "passive"))
      (node (ref "R81") (pin "2") (pinfunction "2_2") (pintype "passive"))
    )
    (net (code "6") (name "/C5") (class "Default")
      (node (ref "D10") (pin "2") (pinfunction "A_2") (pintype "passive"))
      (node (ref "Q8") (pin "2") (pinfunction "S_2") (pintype "passive"))
      (node (ref "R30") (pin "1") (pinfunction "1_1") (pintype "passive"))
      (node (ref "R31") (pin "1") (pinfunction "1_1") (pintype "passive"))
      (node (ref "R80") (pin "2") (pinfunction "2_2") (pintype "passive"))
    )
    (net (code "7") (name "/C6") (class "Default")
      (node (ref "D9") (pin "2") (pinfunction "A_2") (pintype "passive"))
      (node (ref "Q7") (pin "2") (pinfunction "S_2") (pintype "passive"))
      (node (ref "R27") (pin "1") (pinfunction "1_1") (pintype "passive"))
      (node (ref "R28") (pin "1") (pinfunction "1_1") (pintype "passive"))
      (node (ref "R79") (pin "2") (pinfunction "2_2") (pintype "passive"))
    )
    (net (code "8") (name "/C7") (class "Default")
      (node (ref "D8") (pin "2") (pinfunction "A_2") (pintype "passive"))
      (node (ref "Q6") (pin "2") (pinfunction "S_2") (pintype "passive"))
      (node (ref "R24") (pin "1") (pinfunction "1_1") (pintype "passive"))
      (node (ref "R25") (pin "1") (pinfunction "1_1") (pintype "passive"))
      (node (ref "R78") (pin "2") (pinfunction "2_2") (pintype "passive"))
    )
    (net (code "9") (name "/C8") (class "Default")
      (node (ref "D6") (pin "2") (pinfunction "A_2") (pintype "passive"))
      (node (ref "Q5") (pin "2") (pinfunction "S_2") (pintype "passive"))
      (node (ref "R18") (pin "1") (pinfunction "1_1") (pintype "passive"))
      (node (ref "R20") (pin "1") (pinfunction "1_1") (pintype "passive"))
      (node (ref "R21") (pin "1") (pinfunction "1_1") (pintype "passive"))
      (node (ref "R22") (pin "1") (pinfunction "1_1") (pintype "passive"))
      (node (ref "R77") (pin "2") (pinfunction "2_2") (pintype "passive"))
    )
    (net (code "10") (name "/C9") (class "Default")
      (node (ref "D5") (pin "2") (pinfunction "A_2") (pintype "passive"))
      (node (ref "Q4") (pin "2") (pinfunction "S_2") (pintype "passive"))
      (node (ref "R16") (pin "1") (pinfunction "1_1") (pintype "passive"))
      (node (ref "R17") (pin "1") (pinfunction "1_1") (pintype "passive"))
      (node (ref "R76") (pin "2") (pinfunction "2_2") (pintype "passive"))
    )
    (net (code "11") (name "/C10") (class "Default")
      (node (ref "D4") (pin "2") (pinfunction "A_2") (pintype "passive"))
      (node (ref "Q3") (pin "2") (pinfunction "S_2") (pintype "passive"))
      (node (ref "R13") (pin "1") (pinfunction "1_1") (pintype "passive"))
      (node (ref "R14") (pin "1") (pinfunction "1_1") (pintype "passive"))
      (node (ref "R75") (pin "2") (pinfunction "2_2") (pintype "passive"))
    )
    (net (code "12") (name "/C11") (class "Default")
      (node (ref "D3") (pin "2") (pinfunction "A_2") (pintype "passive"))
      (node (ref "Q2") (pin "2") (pinfunction "S_2") (pintype "passive"))
      (node (ref "R10") (pin "1") (pinfunction "1_1") (pintype "passive"))
      (node (ref "R11") (pin "1") (pinfunction "1_1") (pintype "passive"))
      (node (ref "R74") (pin "2") (pinfunction "2_2") (pintype "passive"))
    )
    (net (code "13") (name "/C12") (class "Default")
      (node (ref "R7") (pin "1") (pinfunction "1_1") (pintype "passive"))
      (node (ref "R73") (pin "2") (pinfunction "2_2") (pintype "passive"))
      (node (ref "R8") (pin "1") (pinfunction "1_1") (pintype "passive"))
    )
    (net (code "14") (name "/VC0") (class "Default")
      (node (ref "C28") (pin "2") (pinfunction "2_2") (pintype "passive"))
      (node (ref "R46") (pin "1") (pinfunction "1_1") (pintype "passive"))
      (node (ref "R47") (pin "2") (pinfunction "2_2") (pintype "passive"))
    )
    (net (code "15") (name "/VC1") (class "Default")
      (node (ref "C26") (pin "2") (pinfunction "2_2") (pintype "passive"))
      (node (ref "C27") (pin "1") (pinfunction "1_1") (pintype "passive"))
      (node (ref "R43") (pin "1") (pinfunction "1_1") (pintype "passive"))
      (node (ref "R44") (pin "2") (pinfunction "2_2") (pintype "passive"))
    )
    (net (code "16") (name "/VC2") (class "Default")
      (node (ref "C25") (pin "2") (pinfunction "2_2") (pintype "passive"))
      (node (ref "C26") (pin "1") (pinfunction "1_1") (pintype "passive"))
      (node (ref "R40") (pin "1") (pinfunction "1_1") (pintype "passive"))
      (node (ref "R41") (pin "2") (pinfunction "2_2") (pintype "passive"))
    )
    (net (code "17") (name "/VC4") (class "Default")
      (node (ref "C24") (pin "2") (pinfunction "2_2") (pintype "passive"))
      (node (ref "C25") (pin "1") (pinfunction "1_1") (pintype "passive"))
      (node (ref "R37") (pin "1") (pinfunction "1_1") (pintype "passive"))
      (node (ref "R38") (pin "2") (pinfunction "2_2") (pintype "passive"))
    )
    (net (code "18") (name "/VC5") (class "Default")
      (node (ref "C24") (pin "1") (pinfunction "1_1") (pintype "passive"))
      (node (ref "D12") (pin "2") (pinfunction "A_2") (pintype "passive"))
      (node (ref "R34") (pin "2") (pinfunction "2_2") (pintype "passive"))
    )
    (net (code "19") (name "/VC5B") (class "Default")
      (node (ref "C23") (pin "2") (pinfunction "2_2") (pintype "passive"))
      (node (ref "R33") (pin "1") (pinfunction "1_1") (pintype "passive"))
      (node (ref "R35") (pin "2") (pinfunction "2_2") (pintype "passive"))
    )
    (net (code "20") (name "/VC5x") (class "Default")
      (node (ref "C22") (pin "2") (pinfunction "2_2") (pintype "passive"))
      (node (ref "C23") (pin "1") (pinfunction "1_1") (pintype "passive"))
      (node (ref "D12") (pin "1") (pinfunction "K_1") (pintype "passive"))
      (node (ref "R32") (pin "2") (pinfunction "2_2") (pintype "passive"))
    )
    (net (code "21") (name "/VC6") (class "Default")
      (node (ref "C21") (pin "2") (pinfunction "2_2") (pintype "passive"))
      (node (ref "C22") (pin "1") (pinfunction "1_1") (pintype "passive"))
      (node (ref "R29") (pin "1") (pinfunction "1_1") (pintype "passive"))
      (node (ref "R30") (pin "2") (pinfunction "2_2") (pintype "passive"))
    )
    (net (code "22") (name "/VC7") (class "Default")
      (node (ref "C20") (pin "2") (pinfunction "2_2") (pintype "passive"))
      (node (ref "C21") (pin "1") (pinfunction "1_1") (pintype "passive"))
      (node (ref "R26") (pin "1") (pinfunction "1_1") (pintype "passive"))
      (node (ref "R27") (pin "2") (pinfunction "2_2") (pintype "passive"))
    )
    (net (code "23") (name "/VC9") (class "Default")
      (node (ref "C19") (pin "2") (pinfunction "2_2") (pintype "passive"))
      (node (ref "C20") (pin "1") (pinfunction "1_1") (pintype "passive"))
      (node (ref "R23") (pin "1") (pinfunction "1_1") (pintype "passive"))
      (node (ref "R24") (pin "2") (pinfunction "2_2") (pintype "passive"))
    )
    (net (code "24") (name "/VC10") (class "Default")
      (node (ref "C19") (pin "1") (pinfunction "1_1") (pintype "passive"))
      (node (ref "D7") (pin "2") (pinfunction "A_2") (pintype "passive"))
      (node (ref "R20") (pin "2") (pinfunction "2_2") (pintype "passive"))
    )
    (net (code "25") (name "/VC10B") (class "Default")
      (node (ref "C18") (pin "2") (pinfunction "2_2") (pintype "passive"))
      (node (ref "R19") (pin "1") (pinfunction "1_1") (pintype "passive"))
      (node (ref "R21") (pin "2") (pinfunction "2_2") (pintype "passive"))
    )
    (net (code "26") (name "/VC10x") (class "Default")
      (node (ref "C17") (pin "2") (pinfunction "2_2") (pintype "passive"))
      (node (ref "C18") (pin "1") (pinfunction "1_1") (pintype "passive"))
      (node (ref "D7") (pin "1") (pinfunction "K_1") (pintype "passive"))
      (node (ref "R18") (pin "2") (pinfunction "2_2") (pintype "passive"))
    )
    (net (code "27") (name "/VC11") (class "Default")
      (node (ref "C16") (pin "2") (pinfunction "2_2") (pintype "passive"))
      (node (ref "C17") (pin "1") (pinfunction "1_1") (pintype "passive"))
      (node (ref "R15") (pin "1") (pinfunction "1_1") (pintype "passive"))
      (node (ref "R16") (pin "2") (pinfunction "2_2") (pintype "passive"))
    )
    (net (code "28") (name "/VC12") (class "Default")
      (node (ref "C15") (pin "2") (pinfunction "2_2") (pintype "passive"))
      (node (ref "C16") (pin "1") (pinfunction "1_1") (pintype "passive"))
      (node (ref "R12") (pin "1") (pinfunction "1_1") (pintype "passive"))
      (node (ref "R13") (pin "2") (pinfunction "2_2") (pintype "passive"))
    )
    (net (code "29") (name "/VC14") (class "Default")
      (node (ref "C15") (pin "1") (pinfunction "1_1") (pintype "passive"))
      (node (ref "C38") (pin "2") (pinfunction "2_2") (pintype "passive"))
      (node (ref "R10") (pin "2") (pinfunction "2_2") (pintype "passive"))
      (node (ref "R9") (pin "1") (pinfunction "1_1") (pintype "passive"))
    )
    (net (code "30") (name "/VC15") (class "Default")
      (node (ref "C38") (pin "1") (pinfunction "1_1") (pintype "passive"))
      (node (ref "D2") (pin "2") (pinfunction "A_2") (pintype "passive"))
      (node (ref "R7") (pin "2") (pinfunction "2_2") (pintype "passive"))
    )
    (net (code "31") (name "/VC15x") (class "Default")
      (node (ref "D2") (pin "1") (pinfunction "K_1") (pintype "passive"))
    )
    (net (code "32") (name "GND") (class "Default")
      (node (ref "C27") (pin "2") (pinfunction "2_2") (pintype "passive"))
      (node (ref "C28") (pin "1") (pinfunction "1_1") (pintype "passive"))
    )
    (net (code "33") (name "Net-(D3-K)") (class "Default")
      (node (ref "D3") (pin "1") (pinfunction "K_1") (pintype "passive"))
      (node (ref "Q2") (pin "1") (pinfunction "G_1") (pintype "passive"))
      (node (ref "R9") (pin "2") (pinfunction "2_2") (pintype "passive"))
    )
    (net (code "34") (name "Net-(D4-K)") (class "Default")
      (node (ref "D4") (pin "1") (pinfunction "K_1") (pintype "passive"))
      (node (ref "Q3") (pin "1") (pinfunction "G_1") (pintype "passive"))
      (node (ref "R12") (pin "2") (pinfunction "2_2") (pintype "passive"))
    )
    (net (code "35") (name "Net-(D5-K)") (class "Default")
      (node (ref "D5") (pin "1") (pinfunction "K_1") (pintype "passive"))
      (node (ref "Q4") (pin "1") (pinfunction "G_1") (pintype "passive"))
      (node (ref "R15") (pin "2") (pinfunction "2_2") (pintype "passive"))
    )
    (net (code "36") (name "Net-(D6-K)") (class "Default")
      (node (ref "D6") (pin "1") (pinfunction "K_1") (pintype "passive"))
      (node (ref "Q5") (pin "1") (pinfunction "G_1") (pintype "passive"))
      (node (ref "R19") (pin "2") (pinfunction "2_2") (pintype "passive"))
    )
    (net (code "37") (name "Net-(D8-K)") (class "Default")
      (node (ref "D8") (pin "1") (pinfunction "K_1") (pintype "passive"))
      (node (ref "Q6") (pin "1") (pinfunction "G_1") (pintype "passive"))
      (node (ref "R23") (pin "2") (pinfunction "2_2") (pintype "passive"))
    )
    (net (code "38") (name "Net-(D9-K)") (class "Default")
      (node (ref "D9") (pin "1") (pinfunction "K_1") (pintype "passive"))
      (node (ref "Q7") (pin "1") (pinfunction "G_1") (pintype "passive"))
      (node (ref "R26") (pin "2") (pinfunction "2_2") (pintype "passive"))
    )
    (net (code "39") (name "Net-(D10-K)") (class "Default")
      (node (ref "D10") (pin "1") (pinfunction "K_1") (pintype "passive"))
      (node (ref "Q8") (pin "1") (pinfunction "G_1") (pintype "passive"))
      (node (ref "R29") (pin "2") (pinfunction "2_2") (pintype "passive"))
    )
    (net (code "40") (name "Net-(D11-K)") (class "Default")
      (node (ref "D11") (pin "1") (pinfunction "K_1") (pintype "passive"))
      (node (ref "Q9") (pin "1") (pinfunction "G_1") (pintype "passive"))
      (node (ref "R33") (pin "2") (pinfunction "2_2") (pintype "passive"))
    )
    (net (code "41") (name "Net-(D13-K)") (class "Default")
      (node (ref "D13") (pin "1") (pinfunction "K_1") (pintype "passive"))
      (node (ref "Q10") (pin "1") (pinfunction "G_1") (pintype "passive"))
      (node (ref "R37") (pin "2") (pinfunction "2_2") (pintype "passive"))
    )
    (net (code "42") (name "Net-(D14-K)") (class "Default")
      (node (ref "D14") (pin "1") (pinfunction "K_1") (pintype "passive"))
      (node (ref "Q11") (pin "1") (pinfunction "G_1") (pintype "passive"))
      (node (ref "R40") (pin "2") (pinfunction "2_2") (pintype "passive"))
    )
    (net (code "43") (name "Net-(D15-K)") (class "Default")
      (node (ref "D15") (pin "1") (pinfunction "K_1") (pintype "passive"))
      (node (ref "Q12") (pin "1") (pinfunction "G_1") (pintype "passive"))
      (node (ref "R43") (pin "2") (pinfunction "2_2") (pintype "passive"))
    )
    (net (code "44") (name "Net-(D16-K)") (class "Default")
      (node (ref "D16") (pin "1") (pinfunction "K_1") (pintype "passive"))
      (node (ref "Q13") (pin "1") (pinfunction "G_1") (pintype "passive"))
      (node (ref "R46") (pin "2") (pinfunction "2_2") (pintype "passive"))
    )
    (net (code "45") (name "Net-(D21-PadA)") (class "Default")
      (node (ref "D21") (pin "A") (pinfunction "A_A") (pintype "passive"))
      (node (ref "R73") (pin "1") (pinfunction "1_1") (pintype "passive"))
    )
    (net (code "46") (name "Net-(D22-PadA)") (class "Default")
      (node (ref "D22") (pin "A") (pinfunction "A_A") (pintype "passive"))
      (node (ref "R74") (pin "1") (pinfunction "1_1") (pintype "passive"))
    )
    (net (code "47") (name "Net-(D23-PadA)") (class "Default")
      (node (ref "D23") (pin "A") (pinfunction "A_A") (pintype "passive"))
      (node (ref "R75") (pin "1") (pinfunction "1_1") (pintype "passive"))
    )
    (net (code "48") (name "Net-(D24-PadA)") (class "Default")
      (node (ref "D24") (pin "A") (pinfunction "A_A") (pintype "passive"))
      (node (ref "R76") (pin "1") (pinfunction "1_1") (pintype "passive"))
    )
    (net (code "49") (name "Net-(D25-PadA)") (class "Default")
      (node (ref "D25") (pin "A") (pinfunction "A_A") (pintype "passive"))
      (node (ref "R77") (pin "1") (pinfunction "1_1") (pintype "passive"))
    )
    (net (code "50") (name "Net-(D29-PadA)") (class "Default")
      (node (ref "D29") (pin "A") (pinfunction "A_A") (pintype "passive"))
      (node (ref "R78") (pin "1") (pinfunction "1_1") (pintype "passive"))
    )
    (net (code "51") (name "Net-(D30-PadA)") (class "Default")
      (node (ref "D30") (pin "A") (pinfunction "A_A") (pintype "passive"))
      (node (ref "R79") (pin "1") (pinfunction "1_1") (pintype "passive"))
    )
    (net (code "52") (name "Net-(D31-PadA)") (class "Default")
      (node (ref "D31") (pin "A") (pinfunction "A_A") (pintype "passive"))
      (node (ref "R80") (pin "1") (pinfunction "1_1") (pintype "passive"))
    )
    (net (code "53") (name "Net-(D32-PadA)") (class "Default")
      (node (ref "D32") (pin "A") (pinfunction "A_A") (pintype "passive"))
      (node (ref "R81") (pin "1") (pinfunction "1_1") (pintype "passive"))
    )
    (net (code "54") (name "Net-(D33-PadA)") (class "Default")
      (node (ref "D33") (pin "A") (pinfunction "A_A") (pintype "passive"))
      (node (ref "R82") (pin "1") (pinfunction "1_1") (pintype "passive"))
    )
    (net (code "55") (name "Net-(D34-PadA)") (class "Default")
      (node (ref "D34") (pin "A") (pinfunction "A_A") (pintype "passive"))
      (node (ref "R83") (pin "1") (pinfunction "1_1") (pintype "passive"))
    )
    (net (code "56") (name "Net-(D35-PadA)") (class "Default")
      (node (ref "D35") (pin "A") (pinfunction "A_A") (pintype "passive"))
      (node (ref "R84") (pin "1") (pinfunction "1_1") (pintype "passive"))
    )
    (net (code "57") (name "Net-(Q2-D)") (class "Default")
      (node (ref "D21") (pin "C") (pinfunction "C_C") (pintype "passive"))
      (node (ref "Q2") (pin "3") (pinfunction "D_3") (pintype "passive"))
      (node (ref "R8") (pin "2") (pinfunction "2_2") (pintype "passive"))
    )
    (net (code "58") (name "Net-(Q3-D)") (class "Default")
      (node (ref "D22") (pin "C") (pinfunction "C_C") (pintype "passive"))
      (node (ref "Q3") (pin "3") (pinfunction "D_3") (pintype "passive"))
      (node (ref "R11") (pin "2") (pinfunction "2_2") (pintype "passive"))
    )
    (net (code "59") (name "Net-(Q4-D)") (class "Default")
      (node (ref "D23") (pin "C") (pinfunction "C_C") (pintype "passive"))
      (node (ref "Q4") (pin "3") (pinfunction "D_3") (pintype "passive"))
      (node (ref "R14") (pin "2") (pinfunction "2_2") (pintype "passive"))
    )
    (net (code "60") (name "Net-(Q5-D)") (class "Default")
      (node (ref "D24") (pin "C") (pinfunction "C_C") (pintype "passive"))
      (node (ref "Q5") (pin "3") (pinfunction "D_3") (pintype "passive"))
      (node (ref "R17") (pin "2") (pinfunction "2_2") (pintype "passive"))
    )
    (net (code "61") (name "Net-(Q6-D)") (class "Default")
      (node (ref "D25") (pin "C") (pinfunction "C_C") (pintype "passive"))
      (node (ref "Q6") (pin "3") (pinfunction "D_3") (pintype "passive"))
      (node (ref "R22") (pin "2") (pinfunction "2_2") (pintype "passive"))
    )
    (net (code "62") (name "Net-(Q7-D)") (class "Default")
      (node (ref "D29") (pin "C") (pinfunction "C_C") (pintype "passive"))
      (node (ref "Q7") (pin "3") (pinfunction "D_3") (pintype "passive"))
      (node (ref "R25") (pin "2") (pinfunction "2_2") (pintype "passive"))
    )
    (net (code "63") (name "Net-(Q8-D)") (class "Default")
      (node (ref "D30") (pin "C") (pinfunction "C_C") (pintype "passive"))
      (node (ref "Q8") (pin "3") (pinfunction "D_3") (pintype "passive"))
      (node (ref "R28") (pin "2") (pinfunction "2_2") (pintype "passive"))
    )
    (net (code "64") (name "Net-(Q9-D)") (class "Default")
      (node (ref "D31") (pin "C") (pinfunction "C_C") (pintype "passive"))
      (node (ref "Q9") (pin "3") (pinfunction "D_3") (pintype "passive"))
      (node (ref "R31") (pin "2") (pinfunction "2_2") (pintype "passive"))
    )
    (net (code "65") (name "Net-(Q10-D)") (class "Default")
      (node (ref "D32") (pin "C") (pinfunction "C_C") (pintype "passive"))
      (node (ref "Q10") (pin "3") (pinfunction "D_3") (pintype "passive"))
      (node (ref "R36") (pin "2") (pinfunction "2_2") (pintype "passive"))
    )
    (net (code "66") (name "Net-(Q11-D)") (class "Default")
      (node (ref "D33") (pin "C") (pinfunction "C_C") (pintype "passive"))
      (node (ref "Q11") (pin "3") (pinfunction "D_3") (pintype "passive"))
      (node (ref "R39") (pin "2") (pinfunction "2_2") (pintype "passive"))
    )
    (net (code "67") (name "Net-(Q12-D)") (class "Default")
      (node (ref "D34") (pin "C") (pinfunction "C_C") (pintype "passive"))
      (node (ref "Q12") (pin "3") (pinfunction "D_3") (pintype "passive"))
      (node (ref "R42") (pin "2") (pinfunction "2_2") (pintype "passive"))
    )
    (net (code "68") (name "Net-(Q13-D)") (class "Default")
      (node (ref "D35") (pin "C") (pinfunction "C_C") (pintype "passive"))
      (node (ref "Q13") (pin "3") (pinfunction "D_3") (pintype "passive"))
      (node (ref "R45") (pin "2") (pinfunction "2_2") (pintype "passive"))
    )
  )
)
